# GSM_GNSS_En_Signal_Control.net
KiCad netlist of a schematic drawn in Altium Designer
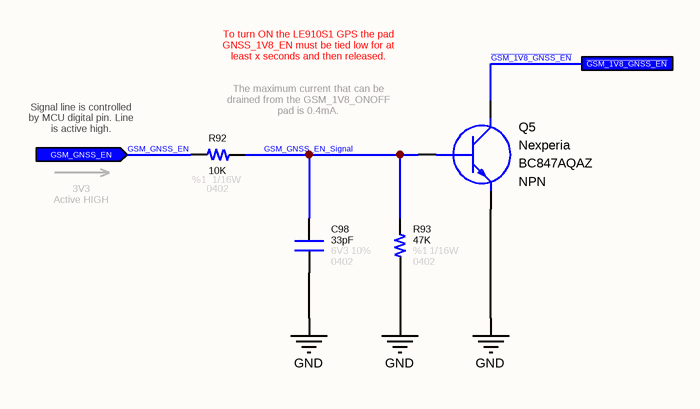
[diagram p0: GSM GNSS En Signal Control.SchDoc]

(export (version "E")
  (design (tool "Eeschema 10.0.6"))
  (components
    (comp (ref "C98")
      (value "33pF")
      (footprint "CAPACITOR_0402")
      (description "Capacitor - 33pF [0402] (Ceramic)")
      (fields
        (field (name "MANUFACTURER PART NUMBER") "C0402C330J9RACAUTO")
        (field (name "TOLERANCE") "10%")
        (field (name "CASE") "0402")
        (field (name "VOLTAGE") "6V3")
      )
      (libsource (lib "Akkoyun") (part "Capacitor - 33pF [0402-6V3]"))
    )
    (comp (ref "Q5")
      (value "BC847AQAZ")
      (footprint "SOT1215")
      (description "Bipolar NPN Transistors")
      (fields
        (field (name "MANUFACTURER NAME") "Nexperia")
        (field (name "MANUFACTURER PART NUMBER") "BC847AQAZ")
        (field (name "POLARITY") "NPN")
      )
      (libsource (lib "Akkoyun") (part "Transistor - BC847"))
    )
    (comp (ref "R92")
      (value "10K")
      (footprint "RESISTOR_0402")
      (description "Thick Film Resistors - SMD 1/16 W 10 KOhm 1%")
      (fields
        (field (name "MANUFACTURER PART NUMBER") "CRCW040210K0FKED")
        (field (name "TOLERANCE") "%1")
        (field (name "CASE") "0402")
        (field (name "POWER") "1/16W")
        (field (name "Comment") "10K - 0402 - %1 - 1/16W")
      )
      (libsource (lib "Akkoyun") (part "Resistor - 10K [0402]"))
    )
    (comp (ref "R93")
      (value "47K")
      (footprint "RESISTOR_0402")
      (description "Thick Film Resistors - SMD 1/16 W 47 KOhm 1%")
      (fields
        (field (name "MANUFACTURER PART NUMBER") "CRCW040247K0FKED")
        (field (name "TOLERANCE") "%1")
        (field (name "CASE") "0402")
        (field (name "POWER") "1/16W")
        (field (name "Comment") "47K - 0402 - %1 - 1/16W")
      )
      (libsource (lib "Akkoyun") (part "Resistor - 47K [0402]"))
    )
  )
  (nets
    (net (code "1") (name "/GSM_GNSS_EN") (class "Default")
      (node (ref "R92") (pin "2") (pinfunction "2_2") (pintype "passive"))
    )
    (net (code "2") (name "/GSM_GNSS_EN_Signal") (class "Default")
      (node (ref "C98") (pin "2") (pinfunction "2_2") (pintype "passive"))
      (node (ref "Q5") (pin "1") (pinfunction "B_1") (pintype "passive"))
      (node (ref "R92") (pin "1") (pinfunction "1_1") (pintype "passive"))
      (node (ref "R93") (pin "2") (pinfunction "2_2") (pintype "passive"))
    )
    (net (code "3") (name "/~{GSM_1V8_GNSS_EN}") (class "Default")
      (node (ref "Q5") (pin "3") (pinfunction "C_3") (pintype "passive"))
    )
    (net (code "4") (name "GND") (class "Default")
      (node (ref "C98") (pin "1") (pinfunction "1_1") (pintype "passive"))
      (node (ref "Q5") (pin "2") (pinfunction "E_2") (pintype "passive"))
      (node (ref "R93") (pin "1") (pinfunction "1_1") (pintype "passive"))
    )
  )
)
